# LPCB235_-_G210_IF_AND_MUX.net
KiCad netlist of a schematic drawn in Altium Designer
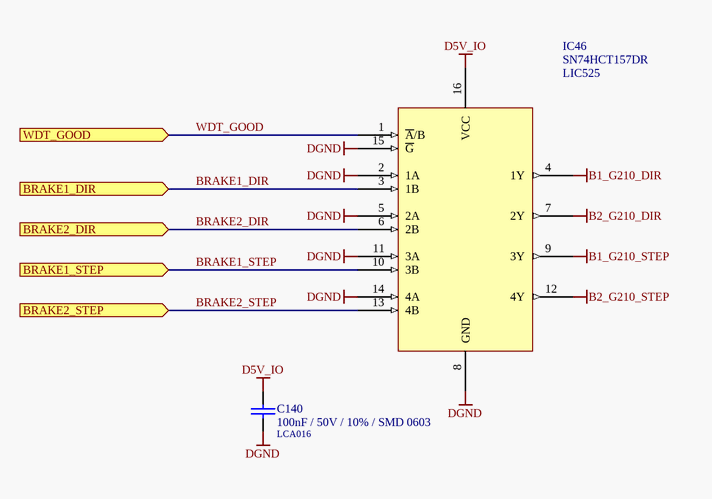
[diagram p0: LPCB235 - G210 IF AND MUX.SchDoc]

(export (version "E")
  (design (tool "Eeschema 10.0.6"))
  (components
    (comp (ref "C140")
      (value "100nF / 50V / 10% / SMD 0603")
      (footprint "LFP011__CC1608-0603-IPC7351_B")
      (description "Capacitor, Ceramic Chip, 100nF (0.1uF), 50V, 5%, SMD 0603 [LCA016]")
      (fields (field (name "LDL_NUMBER") "LCA016"))
      (libsource (lib "LDL_Capacitors") (part "100nF / 50V / 10% / SMD 0603"))
    )
    (comp (ref "IC46")
      (value "SN74HCT157DR")
      (footprint "LFP079__SOP16")
      (description "IC, Multiplexer Select 2-1 [LIC525]")
      (fields (field (name "LDL_NUMBER") "LIC525"))
      (libsource (lib "LDL_Semiconductors") (part "SN74HCT157DR"))
    )
  )
  (nets
    (net (code "1") (name "/BRAKE1_DIR") (class "Default")
      (node (ref "IC46") (pin "3") (pinfunction "1B_3") (pintype "input"))
    )
    (net (code "2") (name "/BRAKE1_STEP") (class "Default")
      (node (ref "IC46") (pin "10") (pinfunction "3B_10") (pintype "input"))
    )
    (net (code "3") (name "/BRAKE2_DIR") (class "Default")
      (node (ref "IC46") (pin "6") (pinfunction "2B_6") (pintype "input"))
    )
    (net (code "4") (name "/BRAKE2_STEP") (class "Default")
      (node (ref "IC46") (pin "13") (pinfunction "4B_13") (pintype "input"))
    )
    (net (code "5") (name "/WDT_GOOD") (class "Default")
      (node (ref "IC46") (pin "1") (pinfunction "~{A}/B_1") (pintype "input"))
    )
    (net (code "6") (name "B1_G210_DIR") (class "Default")
      (node (ref "IC46") (pin "4") (pinfunction "1Y_4") (pintype "output"))
    )
    (net (code "7") (name "B1_G210_STEP") (class "Default")
      (node (ref "IC46") (pin "9") (pinfunction "3Y_9") (pintype "output"))
    )
    (net (code "8") (name "B2_G210_DIR") (class "Default")
      (node (ref "IC46") (pin "7") (pinfunction "2Y_7") (pintype "output"))
    )
    (net (code "9") (name "B2_G210_STEP") (class "Default")
      (node (ref "IC46") (pin "12") (pinfunction "4Y_12") (pintype "output"))
    )
    (net (code "10") (name "D5V_IO") (class "Default")
      (node (ref "C140") (pin "1") (pintype "passive"))
      (node (ref "IC46") (pin "16") (pinfunction "VCC_16") (pintype "power_in"))
    )
    (net (code "11") (name "DGND") (class "Default")
      (node (ref "C140") (pin "2") (pintype "passive"))
      (node (ref "IC46") (pin "11") (pinfunction "3A_11") (pintype "input"))
      (node (ref "IC46") (pin "14") (pinfunction "4A_14") (pintype "input"))
      (node (ref "IC46") (pin "15") (pinfunction "~{G}_15") (pintype "input"))
      (node (ref "IC46") (pin "2") (pinfunction "1A_2") (pintype "input"))
      (node (ref "IC46") (pin "5") (pinfunction "2A_5") (pintype "input"))
      (node (ref "IC46") (pin "8") (pinfunction "GND_8") (pintype "power_in"))
    )
  )
)
